# connector.net
KiCad netlist of a schematic drawn in Altium Designer
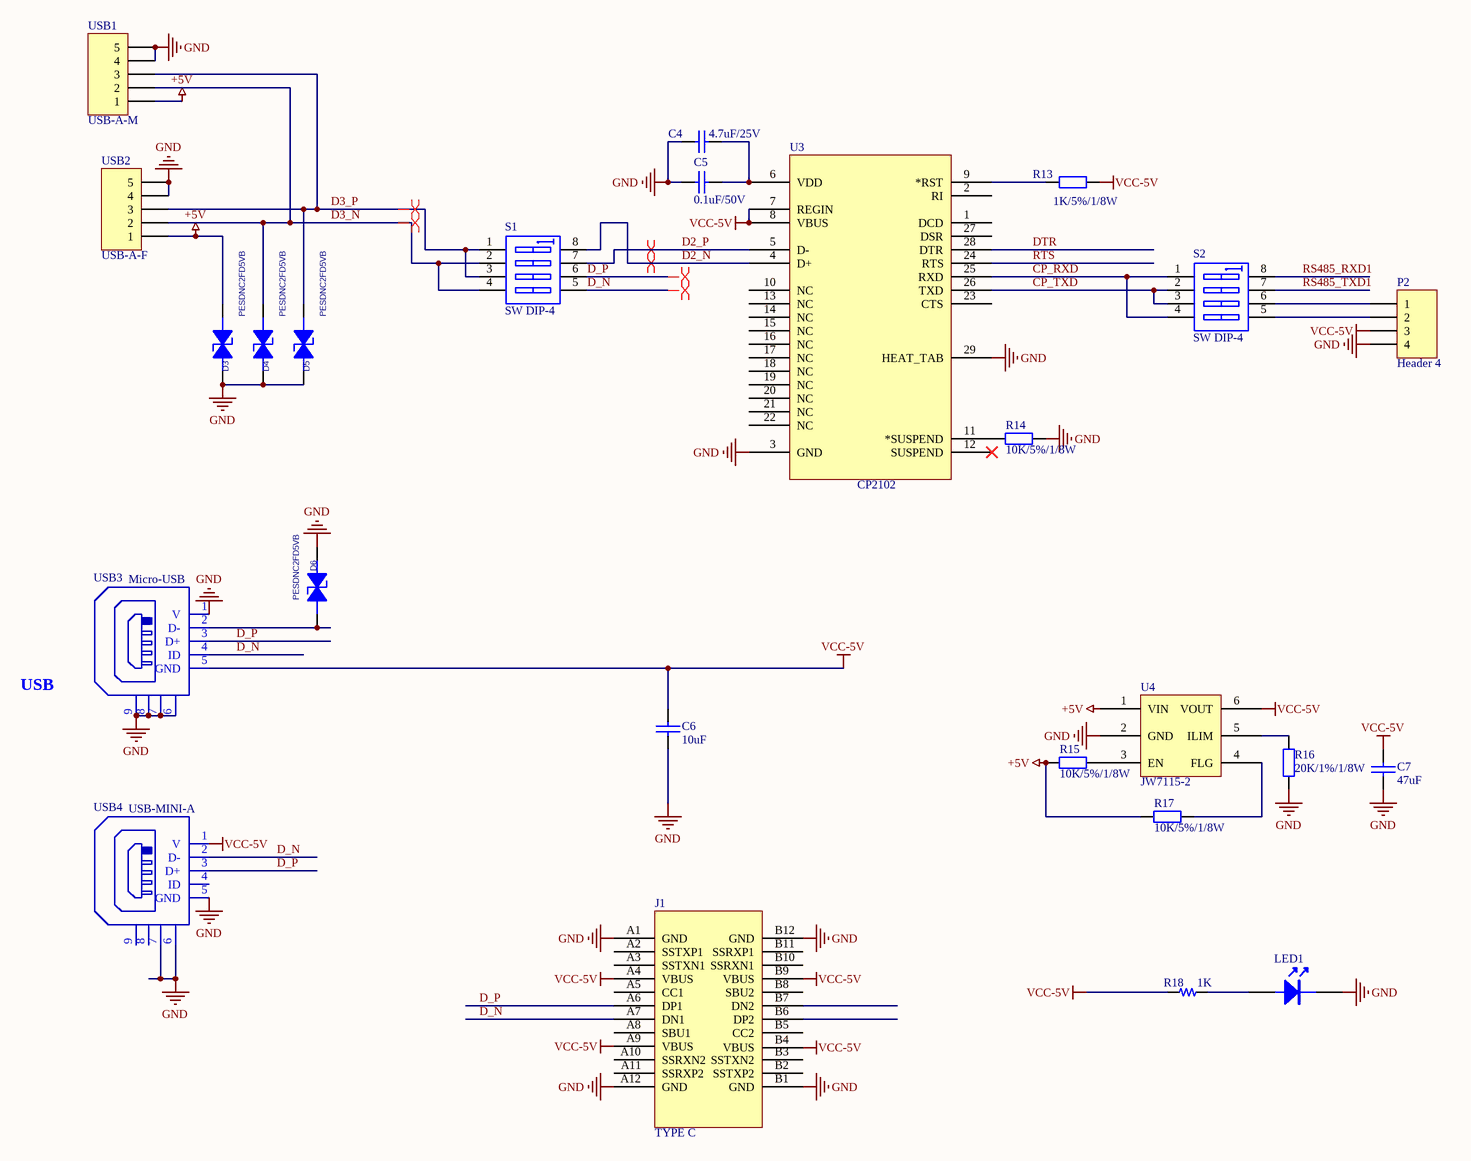
[diagram p0: connector.SchDoc]

(export (version "E")
  (design (tool "Eeschema 10.0.6"))
  (components
    (comp (ref "C4")
      (value "4.7uF/25V")
      (footprint "0603C")
      (description "Capacitor")
      (fields (field (name "PUBLISHER") "Altium Limited"))
      (libsource (lib "Miscellaneous Devices") (part "Cap"))
    )
    (comp (ref "C5")
      (value "0.1uF/50V")
      (footprint "C0603")
      (description "Capacitor")
      (fields (field (name "PUBLISHER") "Altium Limited"))
      (libsource (lib "Miscellaneous Devices") (part "Cap"))
    )
    (comp (ref "C6")
      (value "10uF")
      (footprint "0603C")
      (description "Capacitor")
      (libsource (lib "ZWLIntegrated_Library") (part "CAP"))
    )
    (comp (ref "C7")
      (value "47uF")
      (footprint "0603C")
      (description "Capacitor")
      (libsource (lib "ZWLIntegrated_Library") (part "CAP"))
    )
    (comp (ref "D3")
      (value "PESDNC2FD5VB")
      (footprint "C0402")
      (libsource (lib "*") (part "1_1.5KE100A_Dup1"))
    )
    (comp (ref "D4")
      (value "PESDNC2FD5VB")
      (footprint "C0402")
      (libsource (lib "*") (part "1_1.5KE100A_Dup1"))
    )
    (comp (ref "D5")
      (value "PESDNC2FD5VB")
      (footprint "C0402")
      (libsource (lib "*") (part "1_1.5KE100A_Dup1"))
    )
    (comp (ref "D6")
      (value "PESDNC2FD5VB")
      (footprint "C0402")
      (libsource (lib "*") (part "1_1.5KE100A_Dup1"))
    )
    (comp (ref "J1") (value "TYPE C") (footprint "Type_C-M") (libsource (lib "stm32") (part "TYPE C")))
    (comp (ref "LED1") (value "~") (footprint "0603LED") (libsource (lib "*") (part "LED")))
    (comp (ref "P2")
      (value "Header 4")
      (footprint "HDR1X4")
      (description "Header, 4-Pin")
      (fields (field (name "PUBLISHER") "Altium Limited"))
      (libsource (lib "Miscellaneous Connectors") (part "Header 4"))
    )
    (comp (ref "R13")
      (value "1K/5%/1/8W")
      (footprint "0603R")
      (description "Resistor")
      (fields (field (name "PUBLISHER") "Altium Limited"))
      (libsource (lib "Miscellaneous Devices") (part "Res2"))
    )
    (comp (ref "R14")
      (value "10K/5%/1/8W")
      (footprint "0603R")
      (description "Resistor")
      (fields (field (name "PUBLISHER") "Altium Limited"))
      (libsource (lib "Miscellaneous Devices") (part "Res2"))
    )
    (comp (ref "R15")
      (value "10K/5%/1/8W")
      (footprint "0603R")
      (description "Resistor")
      (fields (field (name "PUBLISHER") "Altium Limited"))
      (libsource (lib "Miscellaneous Devices") (part "Res2"))
    )
    (comp (ref "R16")
      (value "20K/1%/1/8W")
      (footprint "0603R")
      (description "Resistor")
      (fields (field (name "PUBLISHER") "Altium Limited"))
      (libsource (lib "") (part "Res2_1"))
    )
    (comp (ref "R17")
      (value "10K/5%/1/8W")
      (footprint "0603R")
      (description "Resistor")
      (fields (field (name "PUBLISHER") "Altium Limited"))
      (libsource (lib "Miscellaneous Devices") (part "Res2"))
    )
    (comp (ref "R18") (value "1K") (footprint "0603R") (description "R") (libsource (lib "JRJ_1") (part "R")))
    (comp (ref "S1")
      (value "SW DIP-4")
      (footprint "SW_SMT_8")
      (description "DIP Switch, 4 Position, SPST")
      (fields (field (name "PUBLISHER") "Altium Limited"))
      (libsource (lib "Miscellaneous Devices") (part "SW DIP-4"))
    )
    (comp (ref "S2")
      (value "SW DIP-4")
      (footprint "SW_SMT_8")
      (description "DIP Switch, 4 Position, SPST")
      (fields (field (name "PUBLISHER") "Altium Limited"))
      (libsource (lib "Miscellaneous Devices") (part "SW DIP-4"))
    )
    (comp (ref "U3")
      (value "CP2102")
      (footprint "QFN28N5X5-0p5P-L")
      (description "Imported")
      (libsource (lib "stm32") (part "CP2102"))
    )
    (comp (ref "U4") (value "JW7115-2") (footprint "SOT23-6") (libsource (lib "stm32") (part "JW7115-2")))
    (comp (ref "USB1")
      (value "USB-A-M")
      (footprint "USB_A/P_A")
      (description "Header, 5-Pin")
      (fields (field (name "PUBLISHER") "Altium Limited"))
      (libsource (lib "Miscellaneous Connectors") (part "Header 5"))
    )
    (comp (ref "USB2")
      (value "USB-A-F")
      (footprint "USB-A")
      (description "Header, 5-Pin")
      (fields (field (name "PUBLISHER") "Altium Limited"))
      (libsource (lib "Miscellaneous Connectors") (part "Header 5"))
    )
    (comp (ref "USB3") (value "Micro-USB") (footprint "MICRO USB M") (libsource (lib "我的元件库") (part "USB")))
    (comp (ref "USB4") (value "USB-MINI-A") (footprint "MINIUSB-M") (libsource (lib "我的元件库") (part "USB")))
  )
  (nets
    (net (code "1") (name "+5V") (class "Default")
      (node (ref "D3") (pin "1") (pinfunction "ANODE_1") (pintype "passive"))
      (node (ref "R15") (pin "2") (pinfunction "2_2") (pintype "passive"))
      (node (ref "R17") (pin "2") (pinfunction "2_2") (pintype "passive"))
      (node (ref "U4") (pin "1") (pinfunction "VIN_1") (pintype "passive"))
      (node (ref "USB1") (pin "1") (pinfunction "1_1") (pintype "passive"))
      (node (ref "USB2") (pin "1") (pinfunction "1_1") (pintype "passive"))
    )
    (net (code "2") (name "/CP_RXD") (class "Default")
      (node (ref "S2") (pin "1") (pinfunction "A1_1") (pintype "passive"))
      (node (ref "S2") (pin "4") (pinfunction "A4_4") (pintype "passive"))
      (node (ref "U3") (pin "25") (pinfunction "RXD_25") (pintype "passive"))
    )
    (net (code "3") (name "/CP_TXD") (class "Default")
      (node (ref "S2") (pin "2") (pinfunction "A2_2") (pintype "passive"))
      (node (ref "S2") (pin "3") (pinfunction "A3_3") (pintype "passive"))
      (node (ref "U3") (pin "26") (pinfunction "TXD_26") (pintype "passive"))
    )
    (net (code "4") (name "/D2_N") (class "Default")
      (node (ref "S1") (pin "8") (pinfunction "B1_8") (pintype "passive"))
      (node (ref "U3") (pin "4") (pinfunction "D+_4") (pintype "passive"))
    )
    (net (code "5") (name "/D2_P") (class "Default")
      (node (ref "S1") (pin "7") (pinfunction "B2_7") (pintype "passive"))
      (node (ref "U3") (pin "5") (pinfunction "D-_5") (pintype "passive"))
    )
    (net (code "6") (name "/D3_N") (class "Default")
      (node (ref "D4") (pin "1") (pinfunction "ANODE_1") (pintype "passive"))
      (node (ref "S1") (pin "2") (pinfunction "A2_2") (pintype "passive"))
      (node (ref "S1") (pin "4") (pinfunction "A4_4") (pintype "passive"))
      (node (ref "USB1") (pin "2") (pinfunction "2_2") (pintype "passive"))
      (node (ref "USB2") (pin "2") (pinfunction "2_2") (pintype "passive"))
    )
    (net (code "7") (name "/D3_P") (class "Default")
      (node (ref "D5") (pin "1") (pinfunction "ANODE_1") (pintype "passive"))
      (node (ref "S1") (pin "1") (pinfunction "A1_1") (pintype "passive"))
      (node (ref "S1") (pin "3") (pinfunction "A3_3") (pintype "passive"))
      (node (ref "USB1") (pin "3") (pinfunction "3_3") (pintype "passive"))
      (node (ref "USB2") (pin "3") (pinfunction "3_3") (pintype "passive"))
    )
    (net (code "8") (name "/DTR") (class "Default")
      (node (ref "U3") (pin "28") (pinfunction "DTR_28") (pintype "passive"))
    )
    (net (code "9") (name "/D_N") (class "Default")
      (node (ref "J1") (pin "A7") (pinfunction "DN1_A7") (pintype "passive"))
      (node (ref "S1") (pin "5") (pinfunction "B4_5") (pintype "passive"))
      (node (ref "USB3") (pin "4") (pinfunction "ID_4") (pintype "passive"))
      (node (ref "USB4") (pin "2") (pinfunction "D-_2") (pintype "passive"))
    )
    (net (code "10") (name "/D_P") (class "Default")
      (node (ref "J1") (pin "A6") (pinfunction "DP1_A6") (pintype "passive"))
      (node (ref "S1") (pin "6") (pinfunction "B3_6") (pintype "passive"))
      (node (ref "USB3") (pin "3") (pinfunction "D+_3") (pintype "passive"))
      (node (ref "USB4") (pin "3") (pinfunction "D+_3") (pintype "passive"))
    )
    (net (code "11") (name "/RS485_RXD1") (class "Default")
      (node (ref "S2") (pin "8") (pinfunction "B1_8") (pintype "passive"))
    )
    (net (code "12") (name "/RS485_TXD1") (class "Default")
      (node (ref "S2") (pin "7") (pinfunction "B2_7") (pintype "passive"))
    )
    (net (code "13") (name "/RTS") (class "Default")
      (node (ref "U3") (pin "24") (pinfunction "RTS_24") (pintype "passive"))
    )
    (net (code "14") (name "GND") (class "Default")
      (node (ref "C4") (pin "1") (pinfunction "1_1") (pintype "passive"))
      (node (ref "C5") (pin "2") (pinfunction "2_2") (pintype "passive"))
      (node (ref "C6") (pin "1") (pinfunction "1_1") (pintype "passive"))
      (node (ref "C7") (pin "1") (pinfunction "1_1") (pintype "passive"))
      (node (ref "D3") (pin "2") (pinfunction "CATHODE_2") (pintype "passive"))
      (node (ref "D4") (pin "2") (pinfunction "CATHODE_2") (pintype "passive"))
      (node (ref "D5") (pin "2") (pinfunction "CATHODE_2") (pintype "passive"))
      (node (ref "D6") (pin "2") (pinfunction "CATHODE_2") (pintype "passive"))
      (node (ref "J1") (pin "A1") (pinfunction "GND_A1") (pintype "passive"))
      (node (ref "J1") (pin "A12") (pinfunction "GND_A12") (pintype "passive"))
      (node (ref "J1") (pin "B1") (pinfunction "GND_B1") (pintype "passive"))
      (node (ref "J1") (pin "B12") (pinfunction "GND_B12") (pintype "passive"))
      (node (ref "LED1") (pin "2") (pinfunction "2_2") (pintype "passive"))
      (node (ref "P2") (pin "4") (pinfunction "4_4") (pintype "passive"))
      (node (ref "R14") (pin "1") (pinfunction "1_1") (pintype "passive"))
      (node (ref "R16") (pin "2") (pinfunction "2_2") (pintype "passive"))
      (node (ref "U3") (pin "29") (pinfunction "HEAT_TAB_29") (pintype "passive"))
      (node (ref "U3") (pin "3") (pinfunction "GND_3") (pintype "passive"))
      (node (ref "U4") (pin "2") (pinfunction "GND_2") (pintype "passive"))
      (node (ref "USB1") (pin "4") (pinfunction "4_4") (pintype "passive"))
      (node (ref "USB1") (pin "5") (pinfunction "5_5") (pintype "passive"))
      (node (ref "USB2") (pin "4") (pinfunction "4_4") (pintype "passive"))
      (node (ref "USB2") (pin "5") (pinfunction "5_5") (pintype "passive"))
      (node (ref "USB3") (pin "1") (pinfunction "V_1") (pintype "passive"))
      (node (ref "USB3") (pin "6") (pinfunction "6_6") (pintype "passive"))
      (node (ref "USB3") (pin "7") (pinfunction "7_7") (pintype "passive"))
      (node (ref "USB3") (pin "8") (pinfunction "8_8") (pintype "passive"))
      (node (ref "USB3") (pin "9") (pinfunction "9_9") (pintype "passive"))
      (node (ref "USB4") (pin "5") (pinfunction "GND_5") (pintype "passive"))
      (node (ref "USB4") (pin "6") (pinfunction "6_6") (pintype "passive"))
      (node (ref "USB4") (pin "7") (pinfunction "7_7") (pintype "passive"))
    )
    (net (code "15") (name "Net-(D6-ANODE)") (class "Default")
      (node (ref "D6") (pin "1") (pinfunction "ANODE_1") (pintype "passive"))
      (node (ref "USB3") (pin "2") (pinfunction "D-_2") (pintype "passive"))
    )
    (net (code "16") (name "Net-(LED1-Pad1)") (class "Default")
      (node (ref "LED1") (pin "1") (pinfunction "1_1") (pintype "passive"))
      (node (ref "R18") (pin "2") (pintype "passive"))
    )
    (net (code "17") (name "Net-(S2-B3)") (class "Default")
      (node (ref "P2") (pin "1") (pinfunction "1_1") (pintype "passive"))
      (node (ref "S2") (pin "6") (pinfunction "B3_6") (pintype "passive"))
    )
    (net (code "18") (name "Net-(S2-B4)") (class "Default")
      (node (ref "P2") (pin "2") (pinfunction "2_2") (pintype "passive"))
      (node (ref "S2") (pin "5") (pinfunction "B4_5") (pintype "passive"))
    )
    (net (code "19") (name "Net-(U3-*RST)") (class "Default")
      (node (ref "R13") (pin "2") (pinfunction "2_2") (pintype "passive"))
      (node (ref "U3") (pin "9") (pinfunction "*RST_9") (pintype "passive"))
    )
    (net (code "20") (name "Net-(U3-*SUSPEND)") (class "Default")
      (node (ref "R14") (pin "2") (pinfunction "2_2") (pintype "passive"))
      (node (ref "U3") (pin "11") (pinfunction "*SUSPEND_11") (pintype "passive"))
    )
    (net (code "21") (name "Net-(U3-VDD)") (class "Default")
      (node (ref "C4") (pin "2") (pinfunction "2_2") (pintype "passive"))
      (node (ref "C5") (pin "1") (pinfunction "1_1") (pintype "passive"))
      (node (ref "U3") (pin "6") (pinfunction "VDD_6") (pintype "passive"))
    )
    (net (code "22") (name "Net-(U4-EN)") (class "Default")
      (node (ref "R15") (pin "1") (pinfunction "1_1") (pintype "passive"))
      (node (ref "U4") (pin "3") (pinfunction "EN_3") (pintype "passive"))
    )
    (net (code "23") (name "Net-(U4-FLG)") (class "Default")
      (node (ref "R17") (pin "1") (pinfunction "1_1") (pintype "passive"))
      (node (ref "U4") (pin "4") (pinfunction "FLG_4") (pintype "passive"))
    )
    (net (code "24") (name "Net-(U4-ILIM)") (class "Default")
      (node (ref "R16") (pin "1") (pinfunction "1_1") (pintype "passive"))
      (node (ref "U4") (pin "5") (pinfunction "ILIM_5") (pintype "passive"))
    )
    (net (code "25") (name "VCC-5V") (class "Default")
      (node (ref "C6") (pin "2") (pinfunction "2_2") (pintype "passive"))
      (node (ref "C7") (pin "2") (pinfunction "2_2") (pintype "passive"))
      (node (ref "J1") (pin "A4") (pinfunction "VBUS_A4") (pintype "passive"))
      (node (ref "J1") (pin "A9") (pinfunction "VBUS_A9") (pintype "passive"))
      (node (ref "J1") (pin "B4") (pinfunction "VBUS_B4") (pintype "passive"))
      (node (ref "J1") (pin "B9") (pinfunction "VBUS_B9") (pintype "passive"))
      (node (ref "P2") (pin "3") (pinfunction "3_3") (pintype "passive"))
      (node (ref "R13") (pin "1") (pinfunction "1_1") (pintype "passive"))
      (node (ref "R18") (pin "1") (pintype "passive"))
      (node (ref "U3") (pin "7") (pinfunction "REGIN_7") (pintype "passive"))
      (node (ref "U3") (pin "8") (pinfunction "VBUS_8") (pintype "passive"))
      (node (ref "U4") (pin "6") (pinfunction "VOUT_6") (pintype "passive"))
      (node (ref "USB3") (pin "5") (pinfunction "GND_5") (pintype "passive"))
      (node (ref "USB4") (pin "1") (pinfunction "V_1") (pintype "passive"))
    )
    (net (code "26") (name "unconnected-(J1-CC1-PadA5)") (class "Default")
      (node (ref "J1") (pin "A5") (pinfunction "CC1_A5") (pintype "passive"))
    )
    (net (code "27") (name "unconnected-(J1-CC2-PadB5)") (class "Default")
      (node (ref "J1") (pin "B5") (pinfunction "CC2_B5") (pintype "passive"))
    )
    (net (code "28") (name "unconnected-(J1-DN2-PadB7)") (class "Default")
      (node (ref "J1") (pin "B7") (pinfunction "DN2_B7") (pintype "passive"))
    )
    (net (code "29") (name "unconnected-(J1-DP2-PadB6)") (class "Default")
      (node (ref "J1") (pin "B6") (pinfunction "DP2_B6") (pintype "passive"))
    )
    (net (code "30") (name "unconnected-(J1-SBU1-PadA8)") (class "Default")
      (node (ref "J1") (pin "A8") (pinfunction "SBU1_A8") (pintype "passive"))
    )
    (net (code "31") (name "unconnected-(J1-SBU2-PadB8)") (class "Default")
      (node (ref "J1") (pin "B8") (pinfunction "SBU2_B8") (pintype "passive"))
    )
    (net (code "32") (name "unconnected-(J1-SSRXN1-PadB10)") (class "Default")
      (node (ref "J1") (pin "B10") (pinfunction "SSRXN1_B10") (pintype "passive"))
    )
    (net (code "33") (name "unconnected-(J1-SSRXN2-PadA10)") (class "Default")
      (node (ref "J1") (pin "A10") (pinfunction "SSRXN2_A10") (pintype "passive"))
    )
    (net (code "34") (name "unconnected-(J1-SSRXP1-PadB11)") (class "Default")
      (node (ref "J1") (pin "B11") (pinfunction "SSRXP1_B11") (pintype "passive"))
    )
    (net (code "35") (name "unconnected-(J1-SSRXP2-PadA11)") (class "Default")
      (node (ref "J1") (pin "A11") (pinfunction "SSRXP2_A11") (pintype "passive"))
    )
    (net (code "36") (name "unconnected-(J1-SSTXN1-PadA3)") (class "Default")
      (node (ref "J1") (pin "A3") (pinfunction "SSTXN1_A3") (pintype "passive"))
    )
    (net (code "37") (name "unconnected-(J1-SSTXN2-PadB3)") (class "Default")
      (node (ref "J1") (pin "B3") (pinfunction "SSTXN2_B3") (pintype "passive"))
    )
    (net (code "38") (name "unconnected-(J1-SSTXP1-PadA2)") (class "Default")
      (node (ref "J1") (pin "A2") (pinfunction "SSTXP1_A2") (pintype "passive"))
    )
    (net (code "39") (name "unconnected-(J1-SSTXP2-PadB2)") (class "Default")
      (node (ref "J1") (pin "B2") (pinfunction "SSTXP2_B2") (pintype "passive"))
    )
    (net (code "40") (name "unconnected-(U3-CTS-Pad23)") (class "Default")
      (node (ref "U3") (pin "23") (pinfunction "CTS_23") (pintype "passive"))
    )
    (net (code "41") (name "unconnected-(U3-DCD-Pad1)") (class "Default")
      (node (ref "U3") (pin "1") (pinfunction "DCD_1") (pintype "passive"))
    )
    (net (code "42") (name "unconnected-(U3-DSR-Pad27)") (class "Default")
      (node (ref "U3") (pin "27") (pinfunction "DSR_27") (pintype "passive"))
    )
    (net (code "43") (name "unconnected-(U3-NC-Pad10)") (class "Default")
      (node (ref "U3") (pin "10") (pinfunction "NC_10") (pintype "passive"))
    )
    (net (code "44") (name "unconnected-(U3-NC-Pad13)") (class "Default")
      (node (ref "U3") (pin "13") (pinfunction "NC_13") (pintype "passive"))
    )
    (net (code "45") (name "unconnected-(U3-NC-Pad14)") (class "Default")
      (node (ref "U3") (pin "14") (pinfunction "NC_14") (pintype "passive"))
    )
    (net (code "46") (name "unconnected-(U3-NC-Pad15)") (class "Default")
      (node (ref "U3") (pin "15") (pinfunction "NC_15") (pintype "passive"))
    )
    (net (code "47") (name "unconnected-(U3-NC-Pad16)") (class "Default")
      (node (ref "U3") (pin "16") (pinfunction "NC_16") (pintype "passive"))
    )
    (net (code "48") (name "unconnected-(U3-NC-Pad17)") (class "Default")
      (node (ref "U3") (pin "17") (pinfunction "NC_17") (pintype "passive"))
    )
    (net (code "49") (name "unconnected-(U3-NC-Pad18)") (class "Default")
      (node (ref "U3") (pin "18") (pinfunction "NC_18") (pintype "passive"))
    )
    (net (code "50") (name "unconnected-(U3-NC-Pad19)") (class "Default")
      (node (ref "U3") (pin "19") (pinfunction "NC_19") (pintype "passive"))
    )
    (net (code "51") (name "unconnected-(U3-NC-Pad20)") (class "Default")
      (node (ref "U3") (pin "20") (pinfunction "NC_20") (pintype "passive"))
    )
    (net (code "52") (name "unconnected-(U3-NC-Pad21)") (class "Default")
      (node (ref "U3") (pin "21") (pinfunction "NC_21") (pintype "passive"))
    )
    (net (code "53") (name "unconnected-(U3-NC-Pad22)") (class "Default")
      (node (ref "U3") (pin "22") (pinfunction "NC_22") (pintype "passive"))
    )
    (net (code "54") (name "unconnected-(U3-RI-Pad2)") (class "Default")
      (node (ref "U3") (pin "2") (pinfunction "RI_2") (pintype "passive"))
    )
    (net (code "55") (name "unconnected-(U3-SUSPEND-Pad12)") (class "Default")
      (node (ref "U3") (pin "12") (pinfunction "SUSPEND_12") (pintype "passive+no_connect"))
    )
    (net (code "56") (name "unconnected-(USB4-ID-Pad4)") (class "Default")
      (node (ref "USB4") (pin "4") (pinfunction "ID_4") (pintype "passive"))
    )
    (net (code "57") (name "unconnected-(USB4-Pad8)") (class "Default")
      (node (ref "USB4") (pin "8") (pinfunction "8_8") (pintype "passive"))
    )
    (net (code "58") (name "unconnected-(USB4-Pad9)") (class "Default")
      (node (ref "USB4") (pin "9") (pinfunction "9_9") (pintype "passive"))
    )
  )
)
